# Non_Inverting_OpAmp.net
KiCad netlist of a schematic drawn in Altium Designer
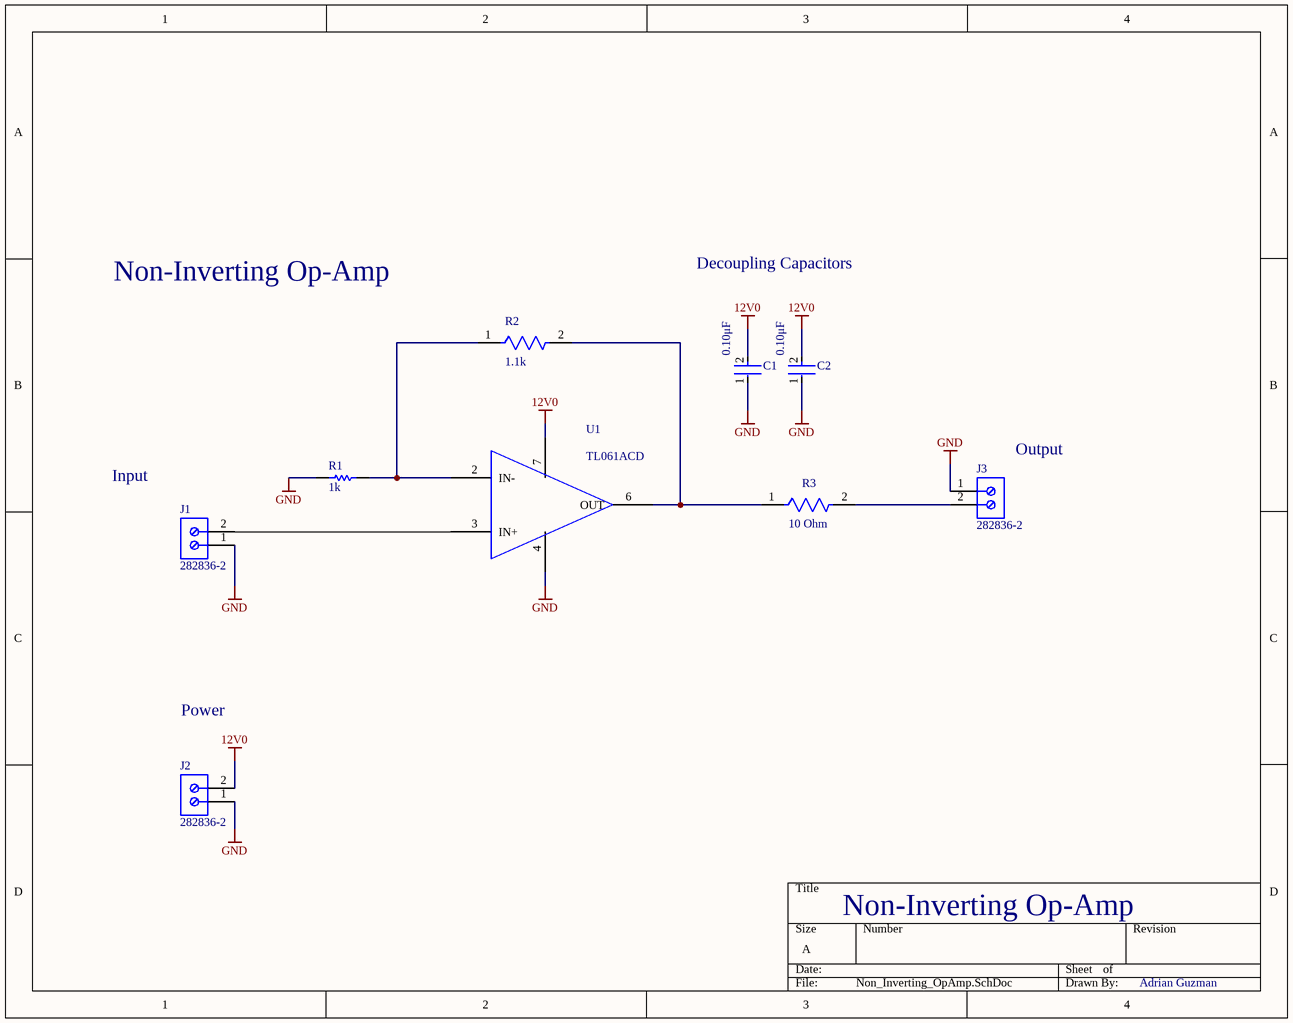
[diagram p0: Non_Inverting_OpAmp.SchDoc]

(export (version "E")
  (design (tool "Eeschema 10.0.6"))
  (components
    (comp (ref "C1")
      (value "GRM155R71C104KA88D")
      (footprint "FP-GRM15-MFG")
      (description "CAP CER 0.1UF 16V X7R 0402")
      (fields
        (field (name "TOLERANCE") "10%")
        (field (name "OCTOPART") "https://octopart.com/grm155r71c104ka88d-murata-196880")
        (field (name "CAPACITANCE") "0.10μF")
      )
      (libsource (lib "Altium Content Vault") (part "236180d848d6139a670b325ea6854c9"))
    )
    (comp (ref "C2")
      (value "GRM155R71C104KA88D")
      (footprint "FP-GRM15-MFG")
      (description "CAP CER 0.1UF 16V X7R 0402")
      (fields
        (field (name "TOLERANCE") "10%")
        (field (name "OCTOPART") "https://octopart.com/grm155r71c104ka88d-murata-196880")
        (field (name "CAPACITANCE") "0.10μF")
      )
      (libsource (lib "Altium Content Vault") (part "236180d848d6139a670b325ea6854c9"))
    )
    (comp (ref "J1")
      (value "282836-2")
      (footprint "TECO-282836-2_V")
      (description "Female Header, Pitch 5 mm, 1 x 2 Position, Height 10 mm, Tail Length 3.5 mm, Rohs, Bulk")
      (fields (field (name "VOLTAGE") "300V") (field (name "MANUFACTURER") "TE Connectivity"))
      (libsource (lib "Altium Content Vault") (part "CN-1P-F-TB2"))
    )
    (comp (ref "J2")
      (value "282836-2")
      (footprint "TECO-282836-2_V")
      (description "Female Header, Pitch 5 mm, 1 x 2 Position, Height 10 mm, Tail Length 3.5 mm, Rohs, Bulk")
      (fields (field (name "VOLTAGE") "300V") (field (name "MANUFACTURER") "TE Connectivity"))
      (libsource (lib "Altium Content Vault") (part "CN-1P-F-TB2"))
    )
    (comp (ref "J3")
      (value "282836-2")
      (footprint "TECO-282836-2_V")
      (description "Female Header, Pitch 5 mm, 1 x 2 Position, Height 10 mm, Tail Length 3.5 mm, Rohs, Bulk")
      (fields (field (name "VOLTAGE") "300V") (field (name "MANUFACTURER") "TE Connectivity"))
      (libsource (lib "Altium Content Vault") (part "CN-1P-F-TB2"))
    )
    (comp (ref "R1")
      (value "ERJ-3EKF1001V")
      (footprint "RESC1608X55X30LL15T15")
      (fields (field (name "MANUFACTURER") "Panasonic") (field (name "RESISTANCE") "1k"))
      (libsource (lib "Altium Content Vault") (part "RES"))
    )
    (comp (ref "R2")
      (value "MCR03EZPFX1101")
      (footprint "FP-MCR03-IPC_B")
      (description "Thick Film Chip Resistor, 0603, 1.1kΩ, 1%, 100ppm/°C, 0.1W, 50V")
      (fields (field (name "TOLERANCE") "1%") (field (name "RESISTANCE") "1.1k"))
      (libsource (lib "Altium Content Vault") (part "1029c3af85768c4190bb7ad29bc67b5"))
    )
    (comp (ref "R3")
      (value "CRCW060310R0FKEA")
      (footprint "FP-CRCW0603-e3-IPC_A")
      (description "RES Thick Film, 10Ω, 1%, 0.1W, 100ppm/°C, 0603")
      (fields (field (name "RESISTANCE") "10 Ohm") (field (name "TOLERANCE") "1%"))
      (libsource (lib "Altium Content Vault") (part "1029c3af85768c4190bb7ad29bc67b5"))
    )
    (comp (ref "U1")
      (value "TL061ACD")
      (footprint "TL061ACD")
      (description "TL061ACD Op-Amp")
      (libsource (lib "TL061ACD_Schematic") (part "TL061ACD"))
    )
  )
  (nets
    (net (code "1") (name "12V0") (class "Default")
      (node (ref "C1") (pin "2") (pinfunction "2_2") (pintype "passive"))
      (node (ref "C2") (pin "2") (pinfunction "2_2") (pintype "passive"))
      (node (ref "J2") (pin "2") (pinfunction "2_2") (pintype "passive"))
      (node (ref "U1") (pin "7") (pinfunction "VCC+_7") (pintype "power_in"))
    )
    (net (code "2") (name "GND") (class "Default")
      (node (ref "C1") (pin "1") (pinfunction "1_1") (pintype "passive"))
      (node (ref "C2") (pin "1") (pinfunction "1_1") (pintype "passive"))
      (node (ref "J1") (pin "1") (pinfunction "1_1") (pintype "passive"))
      (node (ref "J2") (pin "1") (pinfunction "1_1") (pintype "passive"))
      (node (ref "J3") (pin "1") (pinfunction "1_1") (pintype "passive"))
      (node (ref "R1") (pin "2") (pinfunction "2_2") (pintype "passive"))
      (node (ref "U1") (pin "4") (pinfunction "VCC-_4") (pintype "power_in"))
    )
    (net (code "3") (name "Net-(J3-Pad2)") (class "Default")
      (node (ref "J3") (pin "2") (pinfunction "2_2") (pintype "passive"))
      (node (ref "R3") (pin "2") (pinfunction "2_2") (pintype "passive"))
    )
    (net (code "4") (name "Net-(U1-IN+)") (class "Default")
      (node (ref "J1") (pin "2") (pinfunction "2_2") (pintype "passive"))
      (node (ref "U1") (pin "3") (pinfunction "IN+_3") (pintype "passive"))
    )
    (net (code "5") (name "Net-(U1-IN-)") (class "Default")
      (node (ref "R1") (pin "1") (pinfunction "1_1") (pintype "passive"))
      (node (ref "R2") (pin "1") (pinfunction "1_1") (pintype "passive"))
      (node (ref "U1") (pin "2") (pinfunction "IN-_2") (pintype "passive"))
    )
    (net (code "6") (name "Net-(U1-OUT)") (class "Default")
      (node (ref "R2") (pin "2") (pinfunction "2_2") (pintype "passive"))
      (node (ref "R3") (pin "1") (pinfunction "1_1") (pintype "passive"))
      (node (ref "U1") (pin "6") (pinfunction "OUT_6") (pintype "passive"))
    )
  )
)
